# 3_downstream_con.net
KiCad netlist of a schematic drawn in Altium Designer
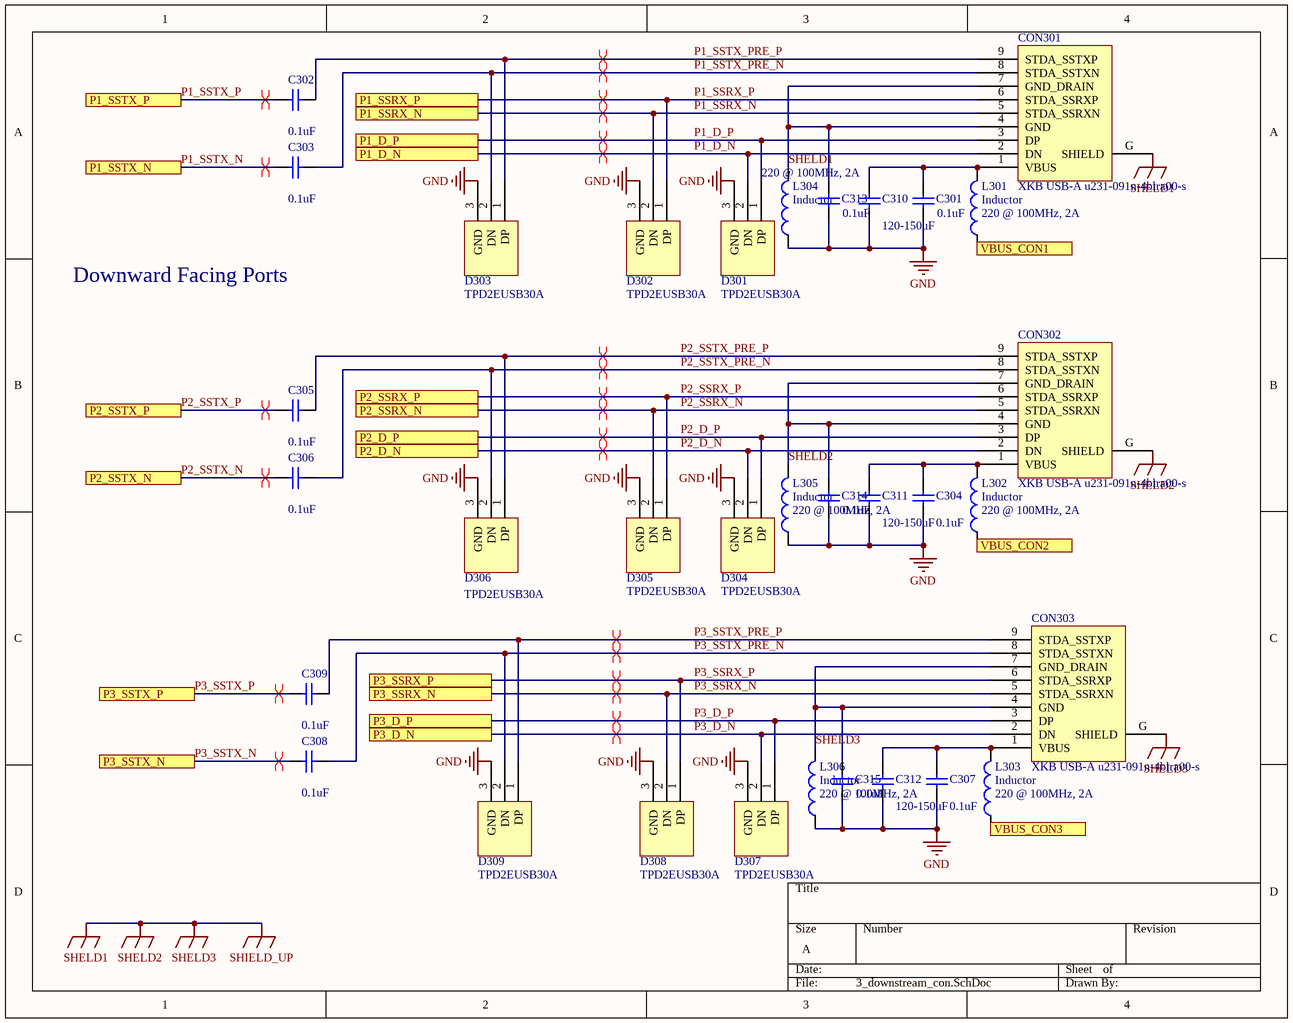
[diagram p0: 3_downstream_con.SchDoc]

(export (version "E")
  (design (tool "Eeschema 10.0.6"))
  (components
    (comp (ref "C301")
      (value "0.1uF")
      (footprint "C0603[1608]")
      (description "Capacitor")
      (fields (field (name "MFG") "KEMET") (field (name "LCSC PART #") "C14663"))
      (libsource (lib "Miscellaneous Devices") (part "Cap"))
    )
    (comp (ref "C302")
      (value "0.1uF")
      (footprint "C0402[1005]")
      (description "Capacitor")
      (fields (field (name "MFG") "KEMET") (field (name "LCSC PART #") "C1525"))
      (libsource (lib "Miscellaneous Devices") (part "Cap"))
    )
    (comp (ref "C303")
      (value "0.1uF")
      (footprint "C0402[1005]")
      (description "Capacitor")
      (fields (field (name "MFG") "KEMET") (field (name "LCSC PART #") "C1525"))
      (libsource (lib "Miscellaneous Devices") (part "Cap"))
    )
    (comp (ref "C304")
      (value "0.1uF")
      (footprint "C0603[1608]")
      (description "Capacitor")
      (fields (field (name "MFG") "KEMET") (field (name "LCSC PART #") "C14663"))
      (libsource (lib "Miscellaneous Devices") (part "Cap"))
    )
    (comp (ref "C305")
      (value "0.1uF")
      (footprint "C0402[1005]")
      (description "Capacitor")
      (fields (field (name "MFG") "KEMET") (field (name "LCSC PART #") "C1525"))
      (libsource (lib "Miscellaneous Devices") (part "Cap"))
    )
    (comp (ref "C306")
      (value "0.1uF")
      (footprint "C0402[1005]")
      (description "Capacitor")
      (fields (field (name "MFG") "KEMET") (field (name "LCSC PART #") "C1525"))
      (libsource (lib "Miscellaneous Devices") (part "Cap"))
    )
    (comp (ref "C307")
      (value "0.1uF")
      (footprint "C0603[1608]")
      (description "Capacitor")
      (fields (field (name "MFG") "KEMET") (field (name "LCSC PART #") "C14663"))
      (libsource (lib "Miscellaneous Devices") (part "Cap"))
    )
    (comp (ref "C308")
      (value "0.1uF")
      (footprint "C0402[1005]")
      (description "Capacitor")
      (fields (field (name "MFG") "KEMET") (field (name "LCSC PART #") "C1525"))
      (libsource (lib "Miscellaneous Devices") (part "Cap"))
    )
    (comp (ref "C309")
      (value "0.1uF")
      (footprint "C0402[1005]")
      (description "Capacitor")
      (fields (field (name "MFG") "KEMET") (field (name "LCSC PART #") "C1525"))
      (libsource (lib "Miscellaneous Devices") (part "Cap"))
    )
    (comp (ref "C310")
      (value "120-150uF")
      (footprint "C_9L_9M")
      (description "Capacitor")
      (fields (field (name "MFG") "Würth Elektronik") (field (name "MRF.PART") "OVZ121M1CTR-0807"))
      (libsource (lib "Miscellaneous Devices") (part "Cap"))
    )
    (comp (ref "C311")
      (value "120-150uF")
      (footprint "C_9L_9M")
      (description "Capacitor")
      (fields (field (name "MFG") "Würth Elektronik") (field (name "MRF.PART") "OVZ121M1CTR-0807"))
      (libsource (lib "Miscellaneous Devices") (part "Cap"))
    )
    (comp (ref "C312")
      (value "120-150uF")
      (footprint "C_9L_9M")
      (description "Capacitor")
      (fields (field (name "MFG") "Würth Elektronik") (field (name "MRF.PART") "OVZ121M1CTR-0807"))
      (libsource (lib "Miscellaneous Devices") (part "Cap"))
    )
    (comp (ref "C313")
      (value "0.1uF")
      (footprint "C0603[1608]")
      (description "Capacitor")
      (fields (field (name "MFG") "KEMET") (field (name "LCSC PART #") "C14663"))
      (libsource (lib "Miscellaneous Devices") (part "Cap"))
    )
    (comp (ref "C314")
      (value "0.1uF")
      (footprint "C0603[1608]")
      (description "Capacitor")
      (fields (field (name "MFG") "KEMET") (field (name "LCSC PART #") "C14663"))
      (libsource (lib "Miscellaneous Devices") (part "Cap"))
    )
    (comp (ref "C315")
      (value "0.1uF")
      (footprint "C0603[1608]")
      (description "Capacitor")
      (fields (field (name "MFG") "KEMET") (field (name "LCSC PART #") "C14663"))
      (libsource (lib "Miscellaneous Devices") (part "Cap"))
    )
    (comp (ref "CON301")
      (value "XKB USB-A u231-091n-4blra00-s")
      (footprint "XKB USB-A u231-091n-4blra00-s")
      (fields (field (name "LCSC PART #") "C381140") (field (name "MRF.PART") "U231-091N-4BLRA00-S-1"))
      (libsource (lib "lib") (part "XKB USB-A u231-091n-4blra00-s"))
    )
    (comp (ref "CON302")
      (value "XKB USB-A u231-091n-4blra00-s")
      (footprint "XKB USB-A u231-091n-4blra00-s")
      (fields (field (name "LCSC PART #") "C381140") (field (name "MRF.PART") "U231-091N-4BLRA00-S-1"))
      (libsource (lib "lib") (part "XKB USB-A u231-091n-4blra00-s"))
    )
    (comp (ref "CON303")
      (value "XKB USB-A u231-091n-4blra00-s")
      (footprint "XKB USB-A u231-091n-4blra00-s")
      (fields (field (name "LCSC PART #") "C381140") (field (name "MRF.PART") "U231-091N-4BLRA00-S-1"))
      (libsource (lib "lib") (part "XKB USB-A u231-091n-4blra00-s"))
    )
    (comp (ref "D301")
      (value "TPD2EUSB30A")
      (footprint "TPD2EUSB30A")
      (fields
        (field (name "MFG") "Texas Instruments")
        (field (name "LCSC PART #") "C94934")
        (field (name "MRF.PART") "TPD2EUSB30ADRTR")
      )
      (libsource (lib "lib") (part "TPD2EUSB30A"))
    )
    (comp (ref "D302")
      (value "TPD2EUSB30A")
      (footprint "TPD2EUSB30A")
      (fields
        (field (name "MFG") "Texas Instruments")
        (field (name "LCSC PART #") "C94934")
        (field (name "MRF.PART") "TPD2EUSB30ADRTR")
      )
      (libsource (lib "lib") (part "TPD2EUSB30A"))
    )
    (comp (ref "D303")
      (value "TPD2EUSB30A")
      (footprint "TPD2EUSB30A")
      (fields
        (field (name "MFG") "Texas Instruments")
        (field (name "LCSC PART #") "C94934")
        (field (name "MRF.PART") "TPD2EUSB30ADRTR")
      )
      (libsource (lib "lib") (part "TPD2EUSB30A"))
    )
    (comp (ref "D304")
      (value "TPD2EUSB30A")
      (footprint "TPD2EUSB30A")
      (fields
        (field (name "MFG") "Texas Instruments")
        (field (name "LCSC PART #") "C94934")
        (field (name "MRF.PART") "TPD2EUSB30ADRTR")
      )
      (libsource (lib "lib") (part "TPD2EUSB30A"))
    )
    (comp (ref "D305")
      (value "TPD2EUSB30A")
      (footprint "TPD2EUSB30A")
      (fields
        (field (name "MFG") "Texas Instruments")
        (field (name "LCSC PART #") "C94934")
        (field (name "MRF.PART") "TPD2EUSB30ADRTR")
      )
      (libsource (lib "lib") (part "TPD2EUSB30A"))
    )
    (comp (ref "D306")
      (value "TPD2EUSB30A")
      (footprint "TPD2EUSB30A")
      (fields
        (field (name "MFG") "Texas Instruments")
        (field (name "LCSC PART #") "C94934")
        (field (name "MRF.PART") "TPD2EUSB30ADRTR")
      )
      (libsource (lib "lib") (part "TPD2EUSB30A"))
    )
    (comp (ref "D307")
      (value "TPD2EUSB30A")
      (footprint "TPD2EUSB30A")
      (fields
        (field (name "MFG") "Texas Instruments")
        (field (name "LCSC PART #") "C94934")
        (field (name "MRF.PART") "TPD2EUSB30ADRTR")
      )
      (libsource (lib "lib") (part "TPD2EUSB30A"))
    )
    (comp (ref "D308")
      (value "TPD2EUSB30A")
      (footprint "TPD2EUSB30A")
      (fields
        (field (name "MFG") "Texas Instruments")
        (field (name "LCSC PART #") "C94934")
        (field (name "MRF.PART") "TPD2EUSB30ADRTR")
      )
      (libsource (lib "lib") (part "TPD2EUSB30A"))
    )
    (comp (ref "D309")
      (value "TPD2EUSB30A")
      (footprint "TPD2EUSB30A")
      (fields
        (field (name "MFG") "Texas Instruments")
        (field (name "LCSC PART #") "C94934")
        (field (name "MRF.PART") "TPD2EUSB30ADRTR")
      )
      (libsource (lib "lib") (part "TPD2EUSB30A"))
    )
    (comp (ref "L301")
      (value "Inductor")
      (footprint "L0603[1608]")
      (fields
        (field (name "ALTIUM_VALUE") "220 @ 100MHz, 2A")
        (field (name "MFG") "Murata Electronics North America")
        (field (name "LCSC PART #") "C85832")
        (field (name "MRF.PART") "BLM18KG331SN1D")
      )
      (libsource (lib "Miscellaneous Devices") (part "Inductor"))
    )
    (comp (ref "L302")
      (value "Inductor")
      (footprint "L0603[1608]")
      (fields
        (field (name "ALTIUM_VALUE") "220 @ 100MHz, 2A")
        (field (name "MFG") "Murata Electronics North America")
        (field (name "LCSC PART #") "C85832")
        (field (name "MRF.PART") "BLM18KG331SN1D")
      )
      (libsource (lib "Miscellaneous Devices") (part "Inductor"))
    )
    (comp (ref "L303")
      (value "Inductor")
      (footprint "L0603[1608]")
      (fields
        (field (name "ALTIUM_VALUE") "220 @ 100MHz, 2A")
        (field (name "MFG") "Murata Electronics North America")
        (field (name "LCSC PART #") "C85832")
        (field (name "MRF.PART") "BLM18KG331SN1D")
      )
      (libsource (lib "Miscellaneous Devices") (part "Inductor"))
    )
    (comp (ref "L304")
      (value "Inductor")
      (footprint "L0603[1608]")
      (fields
        (field (name "ALTIUM_VALUE") "220 @ 100MHz, 2A")
        (field (name "MFG") "Murata Electronics North America")
        (field (name "LCSC PART #") "C85832")
        (field (name "MRF.PART") "BLM18KG331SN1D")
      )
      (libsource (lib "Miscellaneous Devices") (part "Inductor"))
    )
    (comp (ref "L305")
      (value "Inductor")
      (footprint "L0603[1608]")
      (fields
        (field (name "ALTIUM_VALUE") "220 @ 100MHz, 2A")
        (field (name "MFG") "Murata Electronics North America")
        (field (name "LCSC PART #") "C85832")
        (field (name "MRF.PART") "BLM18KG331SN1D")
      )
      (libsource (lib "Miscellaneous Devices") (part "Inductor"))
    )
    (comp (ref "L306")
      (value "Inductor")
      (footprint "L0603[1608]")
      (fields
        (field (name "ALTIUM_VALUE") "220 @ 100MHz, 2A")
        (field (name "MFG") "Murata Electronics North America")
        (field (name "LCSC PART #") "C85832")
        (field (name "MRF.PART") "BLM18KG331SN1D")
      )
      (libsource (lib "Miscellaneous Devices") (part "Inductor"))
    )
  )
  (nets
    (net (code "1") (name "/P1_D_N") (class "Default")
      (node (ref "CON301") (pin "2") (pinfunction "DN_2") (pintype "passive"))
      (node (ref "D301") (pin "2") (pinfunction "DN_2") (pintype "passive"))
    )
    (net (code "2") (name "/P1_D_P") (class "Default")
      (node (ref "CON301") (pin "3") (pinfunction "DP_3") (pintype "passive"))
      (node (ref "D301") (pin "1") (pinfunction "DP_1") (pintype "passive"))
    )
    (net (code "3") (name "/P1_SSRX_N") (class "Default")
      (node (ref "CON301") (pin "5") (pinfunction "STDA_SSRXN_5") (pintype "passive"))
      (node (ref "D302") (pin "2") (pinfunction "DN_2") (pintype "passive"))
    )
    (net (code "4") (name "/P1_SSRX_P") (class "Default")
      (node (ref "CON301") (pin "6") (pinfunction "STDA_SSRXP_6") (pintype "passive"))
      (node (ref "D302") (pin "1") (pinfunction "DP_1") (pintype "passive"))
    )
    (net (code "5") (name "/P1_SSTX_N") (class "Default")
      (node (ref "C303") (pin "2") (pinfunction "2_2") (pintype "passive"))
    )
    (net (code "6") (name "/P1_SSTX_P") (class "Default")
      (node (ref "C302") (pin "2") (pinfunction "2_2") (pintype "passive"))
    )
    (net (code "7") (name "/P1_SSTX_PRE_N") (class "Default")
      (node (ref "C303") (pin "1") (pinfunction "1_1") (pintype "passive"))
      (node (ref "CON301") (pin "8") (pinfunction "STDA_SSTXN_8") (pintype "passive"))
      (node (ref "D303") (pin "2") (pinfunction "DN_2") (pintype "passive"))
    )
    (net (code "8") (name "/P1_SSTX_PRE_P") (class "Default")
      (node (ref "C302") (pin "1") (pinfunction "1_1") (pintype "passive"))
      (node (ref "CON301") (pin "9") (pinfunction "STDA_SSTXP_9") (pintype "passive"))
      (node (ref "D303") (pin "1") (pinfunction "DP_1") (pintype "passive"))
    )
    (net (code "9") (name "/P2_D_N") (class "Default")
      (node (ref "CON302") (pin "2") (pinfunction "DN_2") (pintype "passive"))
      (node (ref "D304") (pin "2") (pinfunction "DN_2") (pintype "passive"))
    )
    (net (code "10") (name "/P2_D_P") (class "Default")
      (node (ref "CON302") (pin "3") (pinfunction "DP_3") (pintype "passive"))
      (node (ref "D304") (pin "1") (pinfunction "DP_1") (pintype "passive"))
    )
    (net (code "11") (name "/P2_SSRX_N") (class "Default")
      (node (ref "CON302") (pin "5") (pinfunction "STDA_SSRXN_5") (pintype "passive"))
      (node (ref "D305") (pin "2") (pinfunction "DN_2") (pintype "passive"))
    )
    (net (code "12") (name "/P2_SSRX_P") (class "Default")
      (node (ref "CON302") (pin "6") (pinfunction "STDA_SSRXP_6") (pintype "passive"))
      (node (ref "D305") (pin "1") (pinfunction "DP_1") (pintype "passive"))
    )
    (net (code "13") (name "/P2_SSTX_N") (class "Default")
      (node (ref "C306") (pin "1") (pinfunction "1_1") (pintype "passive"))
    )
    (net (code "14") (name "/P2_SSTX_P") (class "Default")
      (node (ref "C305") (pin "1") (pinfunction "1_1") (pintype "passive"))
    )
    (net (code "15") (name "/P2_SSTX_PRE_N") (class "Default")
      (node (ref "C306") (pin "2") (pinfunction "2_2") (pintype "passive"))
      (node (ref "CON302") (pin "8") (pinfunction "STDA_SSTXN_8") (pintype "passive"))
      (node (ref "D306") (pin "2") (pinfunction "DN_2") (pintype "passive"))
    )
    (net (code "16") (name "/P2_SSTX_PRE_P") (class "Default")
      (node (ref "C305") (pin "2") (pinfunction "2_2") (pintype "passive"))
      (node (ref "CON302") (pin "9") (pinfunction "STDA_SSTXP_9") (pintype "passive"))
      (node (ref "D306") (pin "1") (pinfunction "DP_1") (pintype "passive"))
    )
    (net (code "17") (name "/P3_D_N") (class "Default")
      (node (ref "CON303") (pin "2") (pinfunction "DN_2") (pintype "passive"))
      (node (ref "D307") (pin "2") (pinfunction "DN_2") (pintype "passive"))
    )
    (net (code "18") (name "/P3_D_P") (class "Default")
      (node (ref "CON303") (pin "3") (pinfunction "DP_3") (pintype "passive"))
      (node (ref "D307") (pin "1") (pinfunction "DP_1") (pintype "passive"))
    )
    (net (code "19") (name "/P3_SSRX_N") (class "Default")
      (node (ref "CON303") (pin "5") (pinfunction "STDA_SSRXN_5") (pintype "passive"))
      (node (ref "D308") (pin "2") (pinfunction "DN_2") (pintype "passive"))
    )
    (net (code "20") (name "/P3_SSRX_P") (class "Default")
      (node (ref "CON303") (pin "6") (pinfunction "STDA_SSRXP_6") (pintype "passive"))
      (node (ref "D308") (pin "1") (pinfunction "DP_1") (pintype "passive"))
    )
    (net (code "21") (name "/P3_SSTX_N") (class "Default")
      (node (ref "C308") (pin "1") (pinfunction "1_1") (pintype "passive"))
    )
    (net (code "22") (name "/P3_SSTX_P") (class "Default")
      (node (ref "C309") (pin "1") (pinfunction "1_1") (pintype "passive"))
    )
    (net (code "23") (name "/P3_SSTX_PRE_N") (class "Default")
      (node (ref "C308") (pin "2") (pinfunction "2_2") (pintype "passive"))
      (node (ref "CON303") (pin "8") (pinfunction "STDA_SSTXN_8") (pintype "passive"))
      (node (ref "D309") (pin "2") (pinfunction "DN_2") (pintype "passive"))
    )
    (net (code "24") (name "/P3_SSTX_PRE_P") (class "Default")
      (node (ref "C309") (pin "2") (pinfunction "2_2") (pintype "passive"))
      (node (ref "CON303") (pin "9") (pinfunction "STDA_SSTXP_9") (pintype "passive"))
      (node (ref "D309") (pin "1") (pinfunction "DP_1") (pintype "passive"))
    )
    (net (code "25") (name "/VBUS_CON1") (class "Default")
      (node (ref "L301") (pin "1") (pinfunction "1_1") (pintype "passive"))
    )
    (net (code "26") (name "/VBUS_CON2") (class "Default")
      (node (ref "L302") (pin "1") (pinfunction "1_1") (pintype "passive"))
    )
    (net (code "27") (name "/VBUS_CON3") (class "Default")
      (node (ref "L303") (pin "1") (pinfunction "1_1") (pintype "passive"))
    )
    (net (code "28") (name "GND") (class "Default")
      (node (ref "C301") (pin "1") (pinfunction "1_1") (pintype "passive"))
      (node (ref "C304") (pin "1") (pinfunction "1_1") (pintype "passive"))
      (node (ref "C307") (pin "1") (pinfunction "1_1") (pintype "passive"))
      (node (ref "C310") (pin "1") (pinfunction "1_1") (pintype "passive"))
      (node (ref "C311") (pin "1") (pinfunction "1_1") (pintype "passive"))
      (node (ref "C312") (pin "1") (pinfunction "1_1") (pintype "passive"))
      (node (ref "C313") (pin "1") (pinfunction "1_1") (pintype "passive"))
      (node (ref "C314") (pin "1") (pinfunction "1_1") (pintype "passive"))
      (node (ref "C315") (pin "1") (pinfunction "1_1") (pintype "passive"))
      (node (ref "D301") (pin "3") (pinfunction "GND_3") (pintype "passive"))
      (node (ref "D302") (pin "3") (pinfunction "GND_3") (pintype "passive"))
      (node (ref "D303") (pin "3") (pinfunction "GND_3") (pintype "passive"))
      (node (ref "D304") (pin "3") (pinfunction "GND_3") (pintype "passive"))
      (node (ref "D305") (pin "3") (pinfunction "GND_3") (pintype "passive"))
      (node (ref "D306") (pin "3") (pinfunction "GND_3") (pintype "passive"))
      (node (ref "D307") (pin "3") (pinfunction "GND_3") (pintype "passive"))
      (node (ref "D308") (pin "3") (pinfunction "GND_3") (pintype "passive"))
      (node (ref "D309") (pin "3") (pinfunction "GND_3") (pintype "passive"))
      (node (ref "L304") (pin "1") (pinfunction "1_1") (pintype "passive"))
      (node (ref "L305") (pin "1") (pinfunction "1_1") (pintype "passive"))
      (node (ref "L306") (pin "1") (pinfunction "1_1") (pintype "passive"))
    )
    (net (code "29") (name "Net-(CON301-VBUS)") (class "Default")
      (node (ref "C301") (pin "2") (pinfunction "2_2") (pintype "passive"))
      (node (ref "C310") (pin "2") (pinfunction "2_2") (pintype "passive"))
      (node (ref "CON301") (pin "1") (pinfunction "VBUS_1") (pintype "passive"))
      (node (ref "L301") (pin "2") (pinfunction "2_2") (pintype "passive"))
    )
    (net (code "30") (name "Net-(CON302-VBUS)") (class "Default")
      (node (ref "C304") (pin "2") (pinfunction "2_2") (pintype "passive"))
      (node (ref "C311") (pin "2") (pinfunction "2_2") (pintype "passive"))
      (node (ref "CON302") (pin "1") (pinfunction "VBUS_1") (pintype "passive"))
      (node (ref "L302") (pin "2") (pinfunction "2_2") (pintype "passive"))
    )
    (net (code "31") (name "Net-(CON303-VBUS)") (class "Default")
      (node (ref "C307") (pin "2") (pinfunction "2_2") (pintype "passive"))
      (node (ref "C312") (pin "2") (pinfunction "2_2") (pintype "passive"))
      (node (ref "CON303") (pin "1") (pinfunction "VBUS_1") (pintype "passive"))
      (node (ref "L303") (pin "2") (pinfunction "2_2") (pintype "passive"))
    )
    (net (code "32") (name "SHELD1") (class "Default")
      (node (ref "C313") (pin "2") (pinfunction "2_2") (pintype "passive"))
      (node (ref "C314") (pin "2") (pinfunction "2_2") (pintype "passive"))
      (node (ref "C315") (pin "2") (pinfunction "2_2") (pintype "passive"))
      (node (ref "CON301") (pin "4") (pinfunction "GND_4") (pintype "passive"))
      (node (ref "CON301") (pin "7") (pinfunction "GND_DRAIN_7") (pintype "passive"))
      (node (ref "CON301") (pin "G") (pinfunction "SHIELD_G") (pintype "passive"))
      (node (ref "CON302") (pin "4") (pinfunction "GND_4") (pintype "passive"))
      (node (ref "CON302") (pin "7") (pinfunction "GND_DRAIN_7") (pintype "passive"))
      (node (ref "CON302") (pin "G") (pinfunction "SHIELD_G") (pintype "passive"))
      (node (ref "CON303") (pin "4") (pinfunction "GND_4") (pintype "passive"))
      (node (ref "CON303") (pin "7") (pinfunction "GND_DRAIN_7") (pintype "passive"))
      (node (ref "CON303") (pin "G") (pinfunction "SHIELD_G") (pintype "passive"))
      (node (ref "L304") (pin "2") (pinfunction "2_2") (pintype "passive"))
      (node (ref "L305") (pin "2") (pinfunction "2_2") (pintype "passive"))
      (node (ref "L306") (pin "2") (pinfunction "2_2") (pintype "passive"))
    )
  )
)
